# GDK.net
KiCad netlist of a schematic drawn in Altium Designer
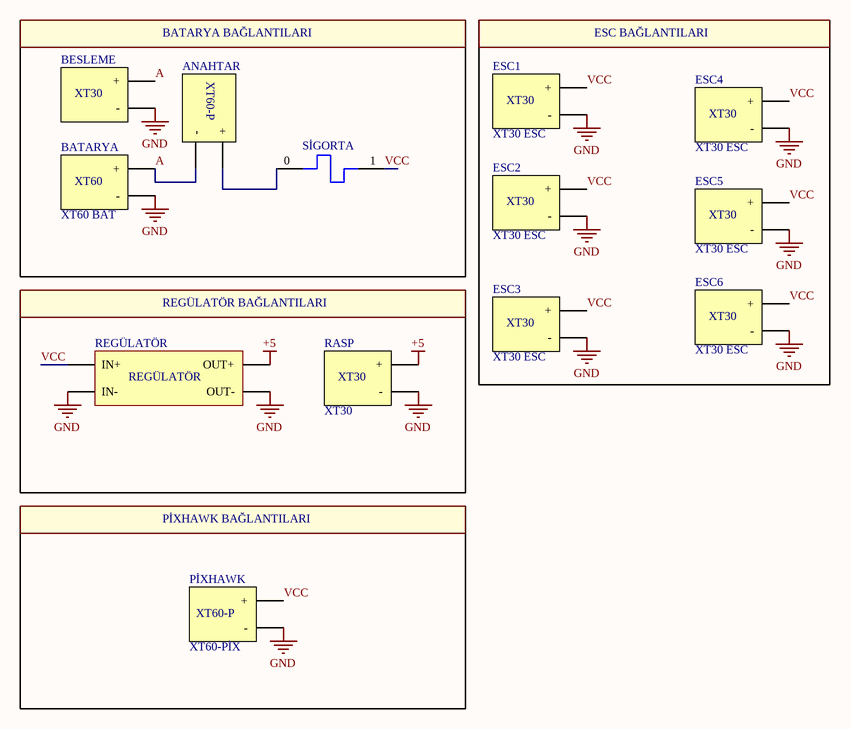
[diagram p0: GDK.SchDoc]

(export (version "E")
  (design (tool "Eeschema 10.0.6"))
  (components
    (comp (ref "ANAHTAR")
      (value "ANAHTAR")
      (footprint "XT60 PİXHAWK")
      (libsource (lib "Schlib2") (part "XT60-PİX"))
    )
    (comp (ref "BATARYA")
      (value "XT60 BAT")
      (footprint "XT60 BATARYA")
      (libsource (lib "Schlib2") (part "XT60 BATARYA"))
    )
    (comp (ref "BESLEME")
      (value "XT30 ESC")
      (footprint "XT30 ESC")
      (libsource (lib "Schlib2") (part "XT30 ESC"))
    )
    (comp (ref "ESC1")
      (value "XT30 ESC")
      (footprint "XT30 ESC")
      (libsource (lib "Schlib2") (part "XT30 ESC"))
    )
    (comp (ref "ESC2")
      (value "XT30 ESC")
      (footprint "XT30 ESC")
      (libsource (lib "Schlib2") (part "XT30 ESC"))
    )
    (comp (ref "ESC3")
      (value "XT30 ESC")
      (footprint "XT30 ESC")
      (libsource (lib "Schlib2") (part "XT30 ESC"))
    )
    (comp (ref "ESC4")
      (value "XT30 ESC")
      (footprint "XT30 ESC")
      (libsource (lib "Schlib2") (part "XT30 ESC"))
    )
    (comp (ref "ESC5")
      (value "XT30 ESC")
      (footprint "XT30 ESC")
      (libsource (lib "Schlib2") (part "XT30 ESC"))
    )
    (comp (ref "ESC6")
      (value "XT30 ESC")
      (footprint "XT30 ESC")
      (libsource (lib "Schlib2") (part "XT30 ESC"))
    )
    (comp (ref "PİXHAWK")
      (value "XT60-PİX")
      (footprint "XT60 PİXHAWK")
      (libsource (lib "Schlib2") (part "XT60-PİXHAWK"))
    )
    (comp (ref "RASP") (value "XT30") (footprint "XT30 ESC") (libsource (lib "Schlib2") (part "XT30")))
    (comp (ref "REGÜLATÖR")
      (value "REGÜLATÖR")
      (footprint "REGÜLATÖR")
      (libsource (lib "Schlib2") (part "REGÜLATÖR"))
    )
    (comp (ref "SİGORTA")
      (value "SİGORTA")
      (footprint "SİGORTA")
      (libsource (lib "Schlib2") (part "SİGORTA"))
    )
  )
  (nets
    (net (code "1") (name "+5") (class "Default")
      (node (ref "RASP") (pin "P") (pinfunction "+_P") (pintype "passive"))
      (node (ref "REGÜLATÖR") (pin "3") (pinfunction "OUT+_3") (pintype "passive"))
    )
    (net (code "2") (name "/A") (class "Default")
      (node (ref "ANAHTAR") (pin "2") (pinfunction "-_2") (pintype "passive"))
      (node (ref "BATARYA") (pin "1") (pinfunction "+_1") (pintype "passive"))
      (node (ref "BESLEME") (pin "P") (pinfunction "+_P") (pintype "passive"))
    )
    (net (code "3") (name "/VCC") (class "Default")
      (node (ref "ESC1") (pin "P") (pinfunction "+_P") (pintype "passive"))
      (node (ref "ESC2") (pin "P") (pinfunction "+_P") (pintype "passive"))
      (node (ref "ESC3") (pin "P") (pinfunction "+_P") (pintype "passive"))
      (node (ref "ESC4") (pin "P") (pinfunction "+_P") (pintype "passive"))
      (node (ref "ESC5") (pin "P") (pinfunction "+_P") (pintype "passive"))
      (node (ref "ESC6") (pin "P") (pinfunction "+_P") (pintype "passive"))
      (node (ref "PİXHAWK") (pin "1") (pinfunction "+_1") (pintype "passive"))
      (node (ref "REGÜLATÖR") (pin "1") (pinfunction "IN+_1") (pintype "passive"))
      (node (ref "SİGORTA") (pin "1") (pintype "passive"))
    )
    (net (code "4") (name "GND") (class "Default")
      (node (ref "BATARYA") (pin "2") (pinfunction "-_2") (pintype "passive"))
      (node (ref "BESLEME") (pin "N") (pinfunction "-_N") (pintype "passive"))
      (node (ref "ESC1") (pin "N") (pinfunction "-_N") (pintype "passive"))
      (node (ref "ESC2") (pin "N") (pinfunction "-_N") (pintype "passive"))
      (node (ref "ESC3") (pin "N") (pinfunction "-_N") (pintype "passive"))
      (node (ref "ESC4") (pin "N") (pinfunction "-_N") (pintype "passive"))
      (node (ref "ESC5") (pin "N") (pinfunction "-_N") (pintype "passive"))
      (node (ref "ESC6") (pin "N") (pinfunction "-_N") (pintype "passive"))
      (node (ref "PİXHAWK") (pin "2") (pinfunction "-_2") (pintype "passive"))
      (node (ref "RASP") (pin "N") (pinfunction "-_N") (pintype "passive"))
      (node (ref "REGÜLATÖR") (pin "2") (pinfunction "IN-_2") (pintype "passive"))
      (node (ref "REGÜLATÖR") (pin "4") (pinfunction "OUT-_4") (pintype "passive"))
    )
    (net (code "5") (name "Net-(ANAHTAR-+)") (class "Default")
      (node (ref "ANAHTAR") (pin "1") (pinfunction "+_1") (pintype "passive"))
      (node (ref "SİGORTA") (pin "0") (pintype "passive"))
    )
  )
)
